# Power-555.net
KiCad netlist of a schematic drawn in Altium Designer
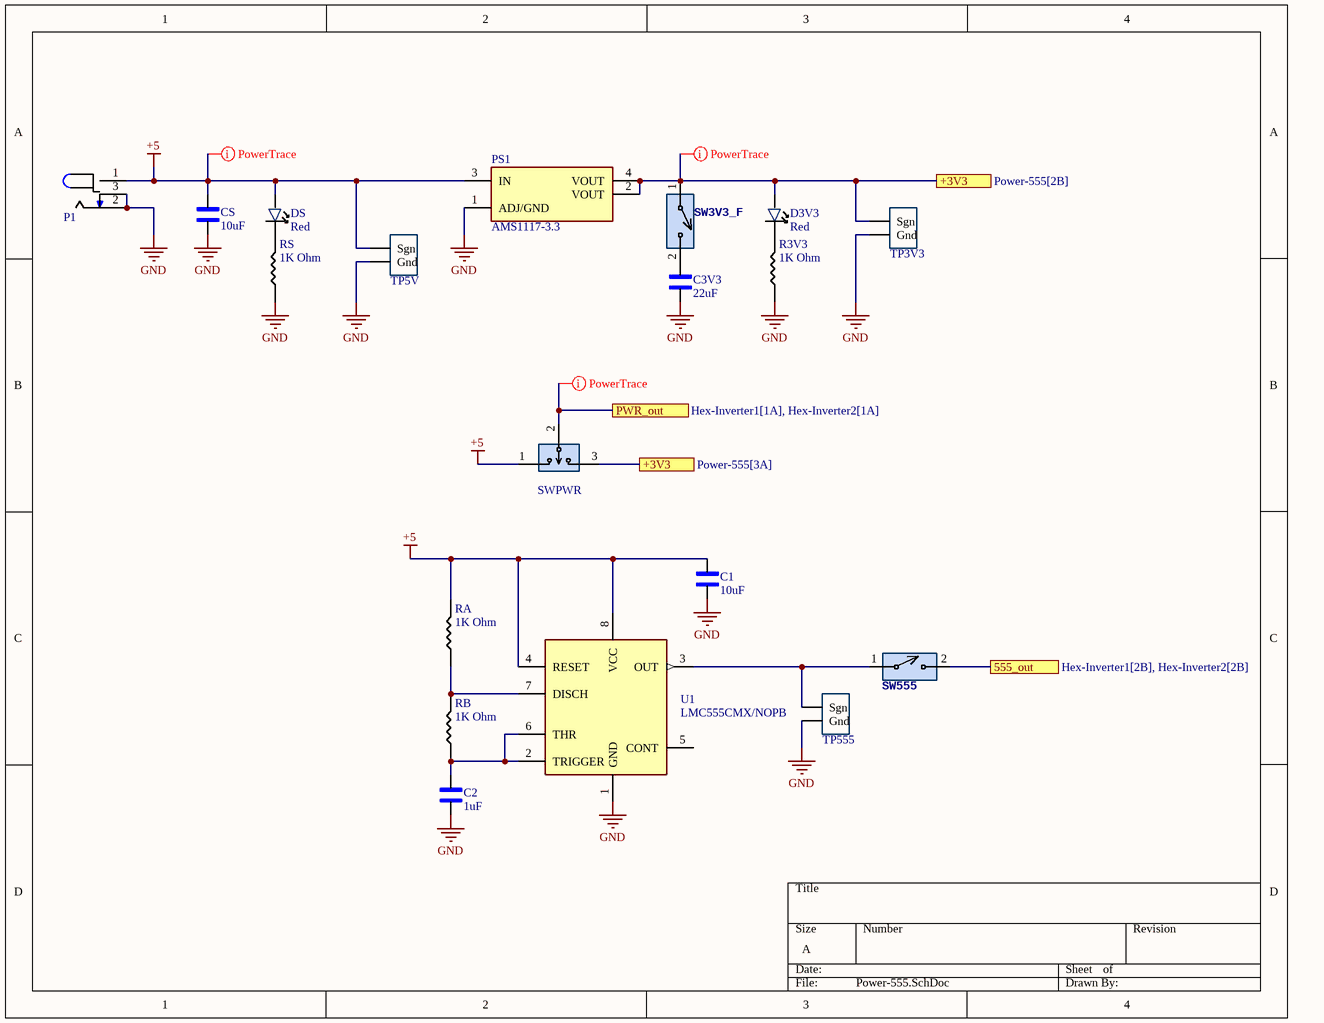
[diagram p0: Power-555.SchDoc]

(export (version "E")
  (design (tool "Eeschema 10.0.6"))
  (components
    (comp (ref "C1")
      (value "10uF")
      (footprint "1206_Passive_Capacitor")
      (description "10uF ±10% 50V X5R 1206 Multilayer Ceramic Capacitors MLCC - SMD/SMT RoHS")
      (fields (field (name "LCSC PART#") "C13585") (field (name "MFR PART #") "CL31A106KBHNNNE"))
      (libsource (lib "ECEN5730Lib") (part "C_10uF_1206"))
    )
    (comp (ref "C2")
      (value "1uF")
      (footprint "1206_Passive_Capacitor")
      (description "MULTILAYER CERAMIC CAPACITORS MLCC - SMD/SMT 1UF 50V 1206 ROHS")
      (fields (field (name "MFR PART #") "CL31B105KBHNNNE") (field (name "LCSC PART#") "C1848"))
      (libsource (lib "ECEN5730Lib") (part "C_1uF_1206"))
    )
    (comp (ref "C3V3")
      (value "22uF")
      (footprint "1206_Passive_Capacitor")
      (description "22uF ±10% 25V X5R 1206 Multilayer Ceramic Capacitors MLCC - SMD/SMT RoHS")
      (fields (field (name "MFR PART #") "CL31A226KAHNNNE") (field (name "LCSC PART#") "C12891"))
      (libsource (lib "ECEN5730Lib") (part "C_22uF_1206"))
    )
    (comp (ref "CS")
      (value "10uF")
      (footprint "1206_Passive_Capacitor")
      (description "10uF ±10% 50V X5R 1206 Multilayer Ceramic Capacitors MLCC - SMD/SMT RoHS")
      (fields (field (name "LCSC PART#") "C13585") (field (name "MFR PART #") "CL31A106KBHNNNE"))
      (libsource (lib "ECEN5730Lib") (part "C_10uF_1206"))
    )
    (comp (ref "D3V3")
      (value "Red")
      (footprint "LED_1206")
      (description "Red 621~631nm 1206 Light Emitting Diodes (LED) RoHS")
      (fields (field (name "MFR PART #") "15-21/R6C-FQ1R1B/2T") (field (name "LCSC PART#") "C93133"))
      (libsource (lib "ECEN5730Lib") (part "LED_RED_1206"))
    )
    (comp (ref "DS")
      (value "Red")
      (footprint "LED_1206")
      (description "Red 621~631nm 1206 Light Emitting Diodes (LED) RoHS")
      (fields (field (name "MFR PART #") "15-21/R6C-FQ1R1B/2T") (field (name "LCSC PART#") "C93133"))
      (libsource (lib "ECEN5730Lib") (part "LED_RED_1206"))
    )
    (comp (ref "P1")
      (value "Power Jack")
      (footprint "Power_Jack")
      (description "Power Barrel Connector Jack 2.10mm ID (0.083\"), 5.50mm OD (0.217\") Through Hole, Right Angle")
      (fields (field (name "MFR PART #") "PJ-102A") (field (name "LCSC PART#") "C136744"))
      (libsource (lib "ECEN5730Lib") (part "P_Power Jack"))
    )
    (comp (ref "PS1")
      (value "AMS1117-3.3")
      (footprint "LDO")
      (description "LOW DROPOUT REGULATORS(LDO) POSITIVE FIXED 1.3V @ 800MA 15V 3.3V 1A SOT-223 ROHS")
      (fields (field (name "LCSC PART#") "C6186"))
      (libsource (lib "ECEN5730Lib") (part "PS_AMS_LDO_3v3"))
    )
    (comp (ref "R3V3")
      (value "1K Ohm")
      (footprint "1206_Passive_Resitor")
      (description "CHIP RESISTOR - SURFACE MOUNT 1KOHMS ±1% 1/4W 1206 ROHS")
      (fields (field (name "MFR PART #") "RNCP1206FTD1K00CT") (field (name "LCSC PART#") "C4410"))
      (libsource (lib "ECEN5730Lib") (part "R_1K_1206"))
    )
    (comp (ref "RA")
      (value "1K Ohm")
      (footprint "1206_Passive_Resitor")
      (description "CHIP RESISTOR - SURFACE MOUNT 1KOHMS ±1% 1/4W 1206 ROHS")
      (fields (field (name "MFR PART #") "RNCP1206FTD1K00CT") (field (name "LCSC PART#") "C4410"))
      (libsource (lib "ECEN5730Lib") (part "R_1K_1206"))
    )
    (comp (ref "RB")
      (value "1K Ohm")
      (footprint "1206_Passive_Resitor")
      (description "CHIP RESISTOR - SURFACE MOUNT 1KOHMS ±1% 1/4W 1206 ROHS")
      (fields (field (name "MFR PART #") "RNCP1206FTD1K00CT") (field (name "LCSC PART#") "C4410"))
      (libsource (lib "ECEN5730Lib") (part "R_1K_1206"))
    )
    (comp (ref "RS")
      (value "1K Ohm")
      (footprint "1206_Passive_Resitor")
      (description "CHIP RESISTOR - SURFACE MOUNT 1KOHMS ±1% 1/4W 1206 ROHS")
      (fields (field (name "MFR PART #") "RNCP1206FTD1K00CT") (field (name "LCSC PART#") "C4410"))
      (libsource (lib "ECEN5730Lib") (part "R_1K_1206"))
    )
    (comp (ref "SW3V3_F")
      (value "SW_2Pin_100mil_Switch")
      (footprint "2Pin-Header-Conn")
      (description "2Pin Header")
      (fields (field (name "LCSC PART#") "C124375"))
      (libsource (lib "ECEN5730Lib") (part "SW_2Pin_100mil_Switch"))
    )
    (comp (ref "SW555")
      (value "SW_2Pin_100mil_Switch")
      (footprint "2Pin-Header-Conn")
      (description "2Pin Header")
      (fields (field (name "LCSC PART#") "C124375"))
      (libsource (lib "") (part "SW_2Pin_100mil_Switch_1"))
    )
    (comp (ref "SWPWR")
      (value "PREC003SAAN-RC")
      (footprint "3_PIN_100mil")
      (description "Connector Header Through Hole 3 position 0.100\" (2.54mm)")
      (fields (field (name "LCSC PART#") "C49257"))
      (libsource (lib "ECEN5730Lib") (part "SW_3Pin_100mil_Switch"))
    )
    (comp (ref "TP3V3")
      (value "10x Probe TP")
      (footprint "TP10x_Probe")
      (description "Test Point 300 mil centers")
      (libsource (lib "ECEN5730Lib") (part "TP_10x_Probe"))
    )
    (comp (ref "TP5V")
      (value "10x Probe TP")
      (footprint "TP10x_Probe")
      (description "Test Point 300 mil centers")
      (libsource (lib "ECEN5730Lib") (part "TP_10x_Probe"))
    )
    (comp (ref "TP555")
      (value "10x Probe TP")
      (footprint "TP10x_Probe")
      (description "Test Point 300 mil centers")
      (libsource (lib "ECEN5730Lib") (part "TP_10x_Probe"))
    )
    (comp (ref "U1")
      (value "LMC555CMX/NOPB")
      (footprint "TS555IDTTR")
      (description "555 Type, Timer/Oscillator _Single_ IC 3MHz 8-SO")
      (fields (field (name "LCSC PART#") "C90760"))
      (libsource (lib "ECEN5730Lib") (part "U_555_Fast"))
    )
  )
  (nets
    (net (code "1") (name "+5") (class "Default")
      (node (ref "C1") (pin "2") (pinfunction "2_2") (pintype "passive"))
      (node (ref "CS") (pin "2") (pinfunction "2_2") (pintype "passive"))
      (node (ref "DS") (pin "1") (pinfunction "1_1") (pintype "passive"))
      (node (ref "P1") (pin "1") (pinfunction "1_1") (pintype "power_in"))
      (node (ref "PS1") (pin "3") (pinfunction "IN_3") (pintype "power_in"))
      (node (ref "RA") (pin "2") (pinfunction "2_2") (pintype "passive"))
      (node (ref "SWPWR") (pin "1") (pinfunction "1_1") (pintype "passive"))
      (node (ref "TP5V") (pin "1") (pinfunction "Sgn_1") (pintype "passive"))
      (node (ref "U1") (pin "4") (pinfunction "RESET_4") (pintype "passive"))
      (node (ref "U1") (pin "8") (pinfunction "VCC_8") (pintype "power_in"))
    )
    (net (code "2") (name "/+3V3") (class "Default")
      (node (ref "D3V3") (pin "1") (pinfunction "1_1") (pintype "passive"))
      (node (ref "PS1") (pin "2") (pinfunction "VOUT_2") (pintype "power_in"))
      (node (ref "PS1") (pin "4") (pinfunction "VOUT_4") (pintype "power_in"))
      (node (ref "SW3V3_F") (pin "1") (pinfunction "1_1") (pintype "passive"))
      (node (ref "SWPWR") (pin "3") (pinfunction "3_3") (pintype "passive"))
      (node (ref "TP3V3") (pin "1") (pinfunction "Sgn_1") (pintype "passive"))
    )
    (net (code "3") (name "/555_out") (class "Default")
      (node (ref "SW555") (pin "2") (pinfunction "2_2") (pintype "passive"))
    )
    (net (code "4") (name "/PWR_out") (class "Default")
      (node (ref "SWPWR") (pin "2") (pinfunction "2_2") (pintype "passive"))
    )
    (net (code "5") (name "GND") (class "Default")
      (node (ref "C1") (pin "1") (pinfunction "1_1") (pintype "passive"))
      (node (ref "C2") (pin "1") (pinfunction "1_1") (pintype "passive"))
      (node (ref "C3V3") (pin "1") (pinfunction "1_1") (pintype "passive"))
      (node (ref "CS") (pin "1") (pinfunction "1_1") (pintype "passive"))
      (node (ref "P1") (pin "2") (pinfunction "2_2") (pintype "power_in"))
      (node (ref "P1") (pin "3") (pinfunction "3_3") (pintype "power_in"))
      (node (ref "PS1") (pin "1") (pinfunction "ADJ/GND_1") (pintype "passive"))
      (node (ref "R3V3") (pin "1") (pinfunction "1_1") (pintype "passive"))
      (node (ref "RS") (pin "1") (pinfunction "1_1") (pintype "passive"))
      (node (ref "TP3V3") (pin "2") (pinfunction "Gnd_2") (pintype "passive"))
      (node (ref "TP555") (pin "2") (pinfunction "Gnd_2") (pintype "passive"))
      (node (ref "TP5V") (pin "2") (pinfunction "Gnd_2") (pintype "passive"))
      (node (ref "U1") (pin "1") (pinfunction "GND_1") (pintype "power_in"))
    )
    (net (code "6") (name "Net-(C3V3-Pad2)") (class "Default")
      (node (ref "C3V3") (pin "2") (pinfunction "2_2") (pintype "passive"))
      (node (ref "SW3V3_F") (pin "2") (pinfunction "2_2") (pintype "passive"))
    )
    (net (code "7") (name "Net-(D3V3-Pad2)") (class "Default")
      (node (ref "D3V3") (pin "2") (pinfunction "2_2") (pintype "passive"))
      (node (ref "R3V3") (pin "2") (pinfunction "2_2") (pintype "passive"))
    )
    (net (code "8") (name "Net-(DS-Pad2)") (class "Default")
      (node (ref "DS") (pin "2") (pinfunction "2_2") (pintype "passive"))
      (node (ref "RS") (pin "2") (pinfunction "2_2") (pintype "passive"))
    )
    (net (code "9") (name "Net-(TP555-Sgn)") (class "Default")
      (node (ref "SW555") (pin "1") (pinfunction "1_1") (pintype "passive"))
      (node (ref "TP555") (pin "1") (pinfunction "Sgn_1") (pintype "passive"))
      (node (ref "U1") (pin "3") (pinfunction "OUT_3") (pintype "output"))
    )
    (net (code "10") (name "Net-(U1-DISCH)") (class "Default")
      (node (ref "RA") (pin "1") (pinfunction "1_1") (pintype "passive"))
      (node (ref "RB") (pin "2") (pinfunction "2_2") (pintype "passive"))
      (node (ref "U1") (pin "7") (pinfunction "DISCH_7") (pintype "passive"))
    )
    (net (code "11") (name "Net-(U1-THR)") (class "Default")
      (node (ref "C2") (pin "2") (pinfunction "2_2") (pintype "passive"))
      (node (ref "RB") (pin "1") (pinfunction "1_1") (pintype "passive"))
      (node (ref "U1") (pin "2") (pinfunction "TRIGGER_2") (pintype "passive"))
      (node (ref "U1") (pin "6") (pinfunction "THR_6") (pintype "passive"))
    )
    (net (code "12") (name "unconnected-(U1-CONT-Pad5)") (class "Default")
      (node (ref "U1") (pin "5") (pinfunction "CONT_5") (pintype "passive"))
    )
  )
)
